# PIC32.net
KiCad netlist of a schematic drawn in EAGLE
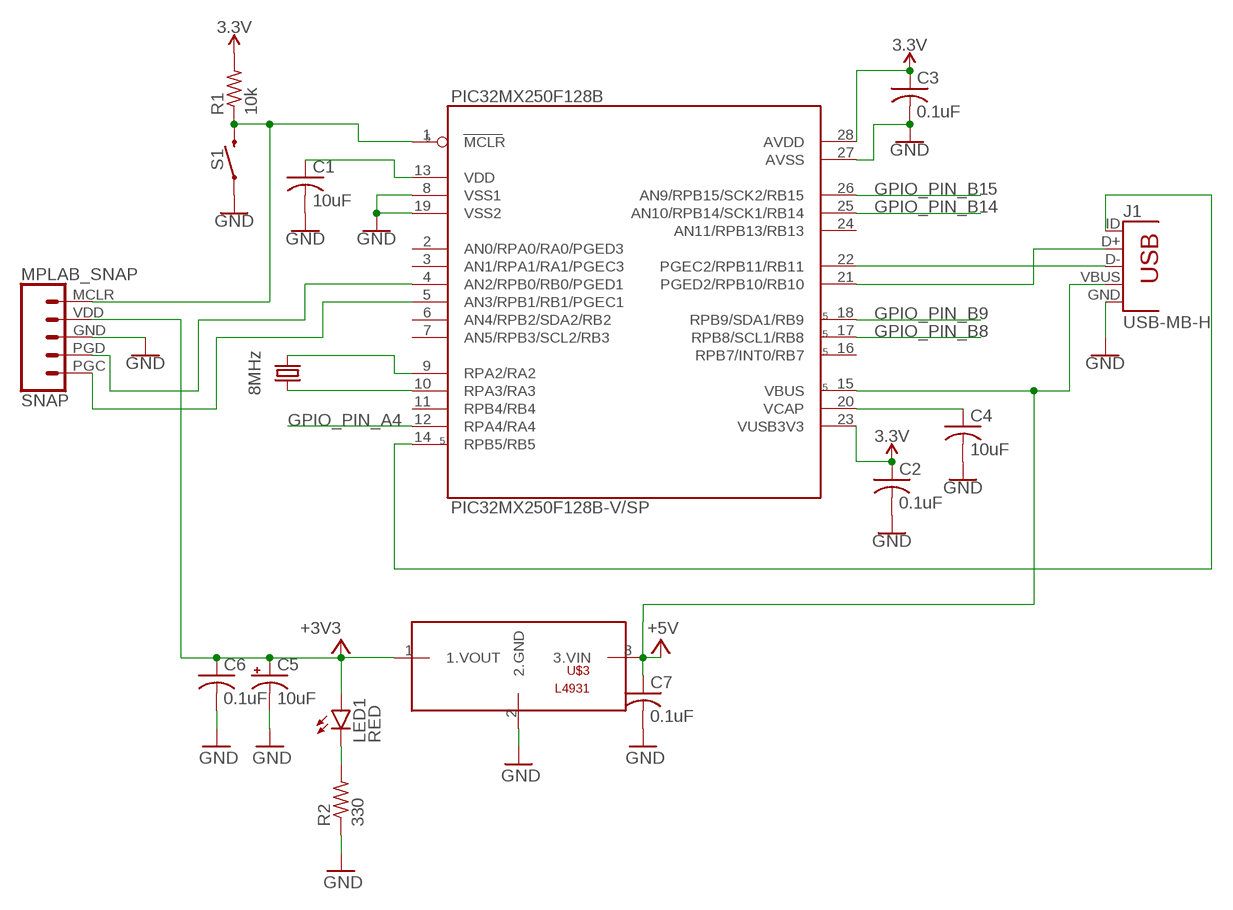
[diagram p0: schematic, sheet 1]

(export (version "E")
  (design (tool "Eeschema 10.0.6"))
  (components
    (comp (ref "C1")
      (value "10uF")
      (footprint "eagle-import:C025-024X044")
      (libsource (lib "eagle-import") (part "C-US025-024X044"))
    )
    (comp (ref "C2")
      (value "0.1uF")
      (footprint "eagle-import:C025-024X044")
      (libsource (lib "eagle-import") (part "C-US025-024X044"))
    )
    (comp (ref "C3")
      (value "0.1uF")
      (footprint "eagle-import:C025-024X044")
      (libsource (lib "eagle-import") (part "C-US025-024X044"))
    )
    (comp (ref "C4")
      (value "10uF")
      (footprint "eagle-import:C025-024X044")
      (libsource (lib "eagle-import") (part "C-US025-024X044"))
    )
    (comp (ref "C5")
      (value "10uF")
      (footprint "eagle-import:B45181B")
      (libsource (lib "eagle-import") (part "CPOL-USB45181B"))
    )
    (comp (ref "C6")
      (value "0.1uF")
      (footprint "eagle-import:C025-025X050")
      (libsource (lib "eagle-import") (part "C-US025-025X050"))
    )
    (comp (ref "C7")
      (value "0.1uF")
      (footprint "eagle-import:C025-025X050")
      (libsource (lib "eagle-import") (part "C-US025-025X050"))
    )
    (comp (ref "J1")
      (value "USB-MB-H")
      (footprint "eagle-import:USB-MB-H")
      (libsource (lib "eagle-import") (part "USB-MB-H"))
    )
    (comp (ref "LED1")
      (value "RED")
      (footprint "eagle-import:LED3MM")
      (fields (field (name "MF") "VISHAY SEMICONDUCTOR"))
      (libsource (lib "eagle-import") (part "TLLR4400"))
    )
    (comp (ref "MPLAB_SNAP")
      (value "SNAP")
      (footprint "eagle-import:SNAP")
      (libsource (lib "eagle-import") (part "SNAP"))
    )
    (comp (ref "PIC32MX250F128B")
      (value "PIC32MX250F128B-V/SP")
      (footprint "eagle-import:DIP254P762X508-28")
      (fields (field (name "MF") "Microchip"))
      (libsource (lib "eagle-import") (part "PIC32MX250F128B-V/SP"))
    )
    (comp (ref "R1")
      (value "10k")
      (footprint "eagle-import:0204V")
      (libsource (lib "eagle-import") (part "R-US_0204/2V"))
    )
    (comp (ref "R2")
      (value "330")
      (footprint "eagle-import:0207_10")
      (libsource (lib "eagle-import") (part "R-US_0207/10"))
    )
    (comp (ref "S1")
      (value "MOMENTARY-SWITCH-SPST-PTH-6.0MM")
      (footprint "eagle-import:TACTILE_SWITCH_PTH_6.0MM")
      (libsource (lib "eagle-import") (part "MOMENTARY-SWITCH-SPST-PTH-6.0MM"))
    )
    (comp (ref "U$3")
      (value "L4931")
      (footprint "eagle-import:TO92-LINE")
      (libsource (lib "eagle-import") (part "L4931"))
    )
    (comp (ref "Y1")
      (value "8MHz")
      (footprint "eagle-import:HC49UP")
      (libsource (lib "eagle-import") (part "CRYSTAL-8MHZSMD-HC49UP"))
    )
  )
  (nets
    (net (code "1") (name "+3V3") (class "Default")
      (node (ref "C5") (pin "+") (pinfunction "+_+") (pintype "passive"))
      (node (ref "C6") (pin "1") (pinfunction "1_1") (pintype "passive"))
      (node (ref "LED1") (pin "A") (pinfunction "A_A") (pintype "passive"))
      (node (ref "MPLAB_SNAP") (pin "VDD") (pinfunction "VDD_VDD") (pintype "passive"))
      (node (ref "U$3") (pin "1") (pinfunction "1.VOUT_1") (pintype "bidirectional"))
    )
    (net (code "2") (name "+5V") (class "Default")
      (node (ref "C7") (pin "1") (pinfunction "1_1") (pintype "passive"))
      (node (ref "J1") (pin "VBUS") (pinfunction "VBUS_VBUS") (pintype "bidirectional"))
      (node (ref "PIC32MX250F128B") (pin "15") (pinfunction "VBUS_15") (pintype "bidirectional"))
      (node (ref "U$3") (pin "3") (pinfunction "3.VIN_3") (pintype "bidirectional"))
    )
    (net (code "3") (name "/GPIO_PIN_A4") (class "Default")
      (node (ref "PIC32MX250F128B") (pin "12") (pinfunction "RPA4/RA4_12") (pintype "bidirectional"))
    )
    (net (code "4") (name "/GPIO_PIN_B8") (class "Default")
      (node (ref "PIC32MX250F128B") (pin "17") (pinfunction "RPB8/SCL1/RB8_17") (pintype "bidirectional"))
    )
    (net (code "5") (name "/GPIO_PIN_B9") (class "Default")
      (node (ref "PIC32MX250F128B") (pin "18") (pinfunction "RPB9/SDA1/RB9_18") (pintype "bidirectional"))
    )
    (net (code "6") (name "/GPIO_PIN_B14") (class "Default")
      (node (ref "PIC32MX250F128B") (pin "25") (pinfunction "AN10/RPB14/SCK1/RB14_25") (pintype "bidirectional"))
    )
    (net (code "7") (name "/GPIO_PIN_B15") (class "Default")
      (node (ref "PIC32MX250F128B") (pin "26") (pinfunction "AN9/RPB15/SCK2/RB15_26") (pintype "bidirectional"))
    )
    (net (code "8") (name "3.3V") (class "Default")
      (node (ref "C2") (pin "1") (pinfunction "1_1") (pintype "passive"))
      (node (ref "C3") (pin "1") (pinfunction "1_1") (pintype "passive"))
      (node (ref "PIC32MX250F128B") (pin "23") (pinfunction "VUSB3V3_23") (pintype "bidirectional"))
      (node (ref "PIC32MX250F128B") (pin "28") (pinfunction "AVDD_28") (pintype "bidirectional"))
      (node (ref "R1") (pin "2") (pinfunction "2_2") (pintype "passive"))
    )
    (net (code "9") (name "GND") (class "Default")
      (node (ref "C1") (pin "2") (pinfunction "2_2") (pintype "passive"))
      (node (ref "C2") (pin "2") (pinfunction "2_2") (pintype "passive"))
      (node (ref "C3") (pin "2") (pinfunction "2_2") (pintype "passive"))
      (node (ref "C4") (pin "2") (pinfunction "2_2") (pintype "passive"))
      (node (ref "C5") (pin "-") (pinfunction "-_-") (pintype "passive"))
      (node (ref "C6") (pin "2") (pinfunction "2_2") (pintype "passive"))
      (node (ref "C7") (pin "2") (pinfunction "2_2") (pintype "passive"))
      (node (ref "J1") (pin "GND") (pinfunction "GND_GND") (pintype "bidirectional"))
      (node (ref "MPLAB_SNAP") (pin "GND") (pinfunction "GND_GND") (pintype "passive"))
      (node (ref "PIC32MX250F128B") (pin "19") (pinfunction "VSS2_19") (pintype "bidirectional"))
      (node (ref "PIC32MX250F128B") (pin "27") (pinfunction "AVSS_27") (pintype "bidirectional"))
      (node (ref "PIC32MX250F128B") (pin "8") (pinfunction "VSS1_8") (pintype "bidirectional"))
      (node (ref "R2") (pin "1") (pinfunction "1_1") (pintype "passive"))
      (node (ref "S1") (pin "1") (pinfunction "1_1") (pintype "passive"))
      (node (ref "U$3") (pin "2") (pinfunction "2.GND_2") (pintype "bidirectional"))
    )
    (net (code "10") (name "Net-(LED1-C)") (class "Default")
      (node (ref "LED1") (pin "K") (pinfunction "C_K") (pintype "passive"))
      (node (ref "R2") (pin "2") (pinfunction "2_2") (pintype "passive"))
    )
    (net (code "11") (name "Net-(PIC32MX250F128B-AN2{slash}RPB0{slash}RB0{slash}PGED1)") (class "Default")
      (node (ref "MPLAB_SNAP") (pin "PGD") (pinfunction "PGD_PGD") (pintype "passive"))
      (node (ref "PIC32MX250F128B") (pin "4") (pinfunction "AN2/RPB0/RB0/PGED1_4") (pintype "bidirectional"))
    )
    (net (code "12") (name "Net-(PIC32MX250F128B-AN3{slash}RPB1{slash}RB1{slash}PGEC1)") (class "Default")
      (node (ref "MPLAB_SNAP") (pin "PGC") (pinfunction "PGC_PGC") (pintype "passive"))
      (node (ref "PIC32MX250F128B") (pin "5") (pinfunction "AN3/RPB1/RB1/PGEC1_5") (pintype "bidirectional"))
    )
    (net (code "13") (name "Net-(PIC32MX250F128B-MCLR)") (class "Default")
      (node (ref "MPLAB_SNAP") (pin "MCLR") (pinfunction "MCLR_MCLR") (pintype "passive"))
      (node (ref "PIC32MX250F128B") (pin "1") (pinfunction "MCLR_1") (pintype "bidirectional"))
      (node (ref "R1") (pin "1") (pinfunction "1_1") (pintype "passive"))
      (node (ref "S1") (pin "3") (pinfunction "2_3") (pintype "passive"))
    )
    (net (code "14") (name "Net-(PIC32MX250F128B-PGEC2{slash}RPB11{slash}RB11)") (class "Default")
      (node (ref "J1") (pin "D-") (pinfunction "D-_D-") (pintype "bidirectional"))
      (node (ref "PIC32MX250F128B") (pin "22") (pinfunction "PGEC2/RPB11/RB11_22") (pintype "bidirectional"))
    )
    (net (code "15") (name "Net-(PIC32MX250F128B-PGED2{slash}RPB10{slash}RB10)") (class "Default")
      (node (ref "J1") (pin "D+") (pinfunction "D+_D+") (pintype "bidirectional"))
      (node (ref "PIC32MX250F128B") (pin "21") (pinfunction "PGED2/RPB10/RB10_21") (pintype "bidirectional"))
    )
    (net (code "16") (name "Net-(PIC32MX250F128B-RPA2{slash}RA2)") (class "Default")
      (node (ref "PIC32MX250F128B") (pin "9") (pinfunction "RPA2/RA2_9") (pintype "bidirectional"))
      (node (ref "Y1") (pin "2") (pinfunction "2_2") (pintype "passive"))
    )
    (net (code "17") (name "Net-(PIC32MX250F128B-RPA3{slash}RA3)") (class "Default")
      (node (ref "PIC32MX250F128B") (pin "10") (pinfunction "RPA3/RA3_10") (pintype "bidirectional"))
      (node (ref "Y1") (pin "1") (pinfunction "1_1") (pintype "passive"))
    )
    (net (code "18") (name "Net-(PIC32MX250F128B-RPB5{slash}RB5)") (class "Default")
      (node (ref "J1") (pin "ID") (pinfunction "ID_ID") (pintype "bidirectional"))
      (node (ref "PIC32MX250F128B") (pin "14") (pinfunction "RPB5/RB5_14") (pintype "bidirectional"))
    )
    (net (code "19") (name "Net-(PIC32MX250F128B-VCAP)") (class "Default")
      (node (ref "C4") (pin "1") (pinfunction "1_1") (pintype "passive"))
      (node (ref "PIC32MX250F128B") (pin "20") (pinfunction "VCAP_20") (pintype "bidirectional"))
    )
    (net (code "20") (name "Net-(PIC32MX250F128B-VDD)") (class "Default")
      (node (ref "C1") (pin "1") (pinfunction "1_1") (pintype "passive"))
      (node (ref "PIC32MX250F128B") (pin "13") (pinfunction "VDD_13") (pintype "bidirectional"))
    )
    (net (code "21") (name "unconnected-(PIC32MX250F128B-AN0{slash}RPA0{slash}RA0{slash}PGED3-Pad2)") (class "Default")
      (node (ref "PIC32MX250F128B") (pin "2") (pinfunction "AN0/RPA0/RA0/PGED3_2") (pintype "bidirectional"))
    )
    (net (code "22") (name "unconnected-(PIC32MX250F128B-AN1{slash}RPA1{slash}RA1{slash}PGEC3-Pad3)") (class "Default")
      (node (ref "PIC32MX250F128B") (pin "3") (pinfunction "AN1/RPA1/RA1/PGEC3_3") (pintype "bidirectional"))
    )
    (net (code "23") (name "unconnected-(PIC32MX250F128B-AN4{slash}RPB2{slash}SDA2{slash}RB2-Pad6)") (class "Default")
      (node (ref "PIC32MX250F128B") (pin "6") (pinfunction "AN4/RPB2/SDA2/RB2_6") (pintype "bidirectional"))
    )
    (net (code "24") (name "unconnected-(PIC32MX250F128B-AN5{slash}RPB3{slash}SCL2{slash}RB3-Pad7)") (class "Default")
      (node (ref "PIC32MX250F128B") (pin "7") (pinfunction "AN5/RPB3/SCL2/RB3_7") (pintype "bidirectional"))
    )
    (net (code "25") (name "unconnected-(PIC32MX250F128B-AN11{slash}RPB13{slash}RB13-Pad24)") (class "Default")
      (node (ref "PIC32MX250F128B") (pin "24") (pinfunction "AN11/RPB13/RB13_24") (pintype "bidirectional"))
    )
    (net (code "26") (name "unconnected-(PIC32MX250F128B-RPB4{slash}RB4-Pad11)") (class "Default")
      (node (ref "PIC32MX250F128B") (pin "11") (pinfunction "RPB4/RB4_11") (pintype "bidirectional"))
    )
    (net (code "27") (name "unconnected-(PIC32MX250F128B-RPB7{slash}INT0{slash}RB7-Pad16)") (class "Default")
      (node (ref "PIC32MX250F128B") (pin "16") (pinfunction "RPB7/INT0/RB7_16") (pintype "bidirectional"))
    )
  )
)
